# untitled.net
KiCad netlist of a schematic drawn in EAGLE
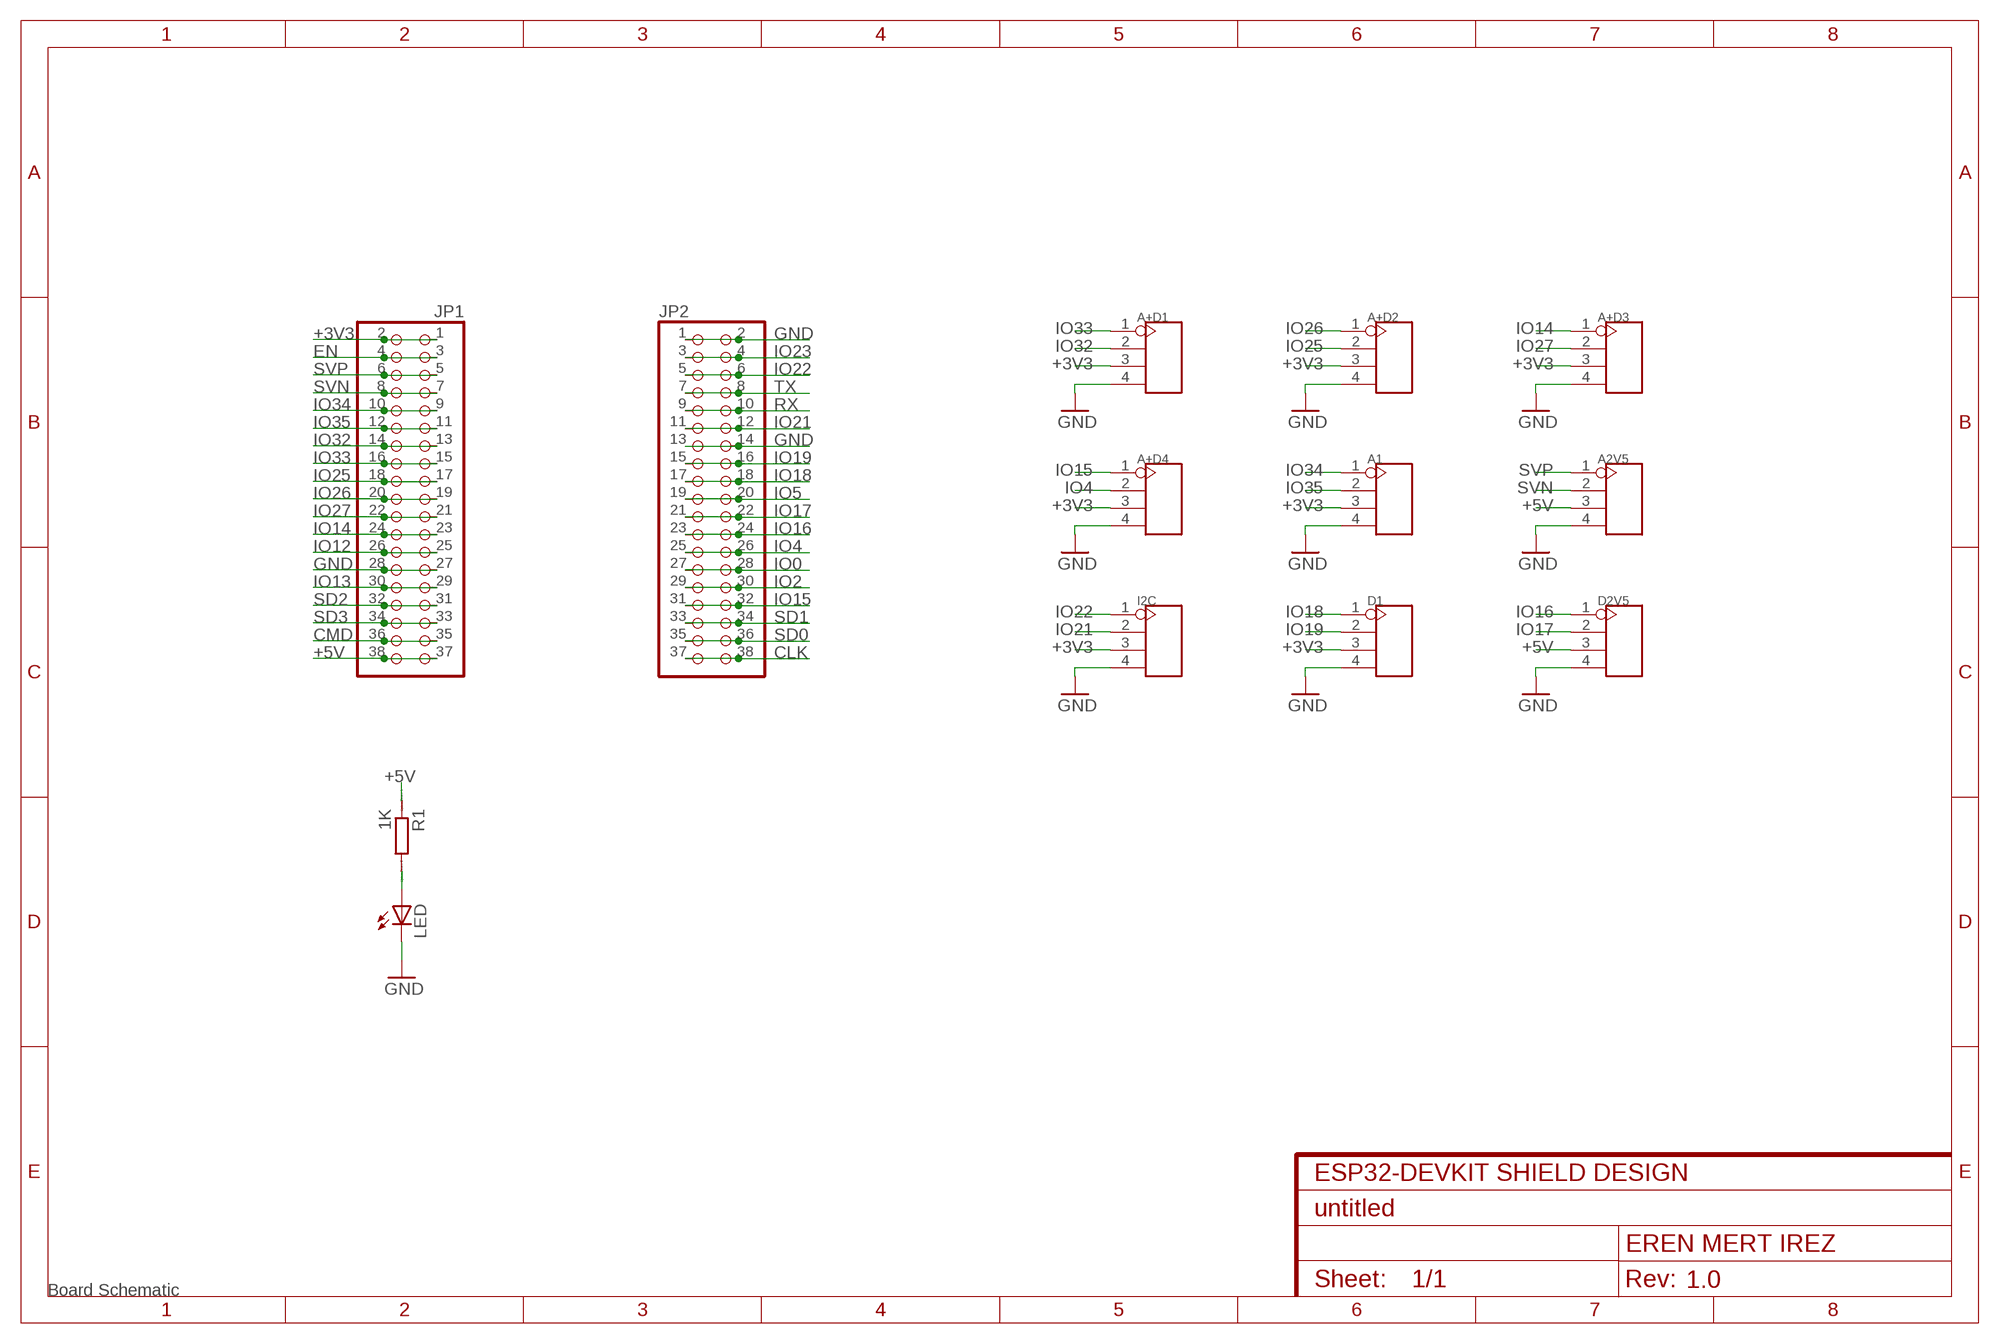
[diagram p0: schematic, sheet 1]

(export (version "E")
  (design (tool "Eeschema 10.0.6"))
  (components
    (comp (ref "A+D1")
      (value "HEADER-4P-80/40MIL")
      (footprint "eagle-import:4P-2.54-80_40MIL")
      (libsource (lib "eagle-import") (part "HEADER-4P-80/40MIL"))
    )
    (comp (ref "A+D2")
      (value "HEADER-4P-80/40MIL")
      (footprint "eagle-import:4P-2.54-80_40MIL")
      (libsource (lib "eagle-import") (part "HEADER-4P-80/40MIL"))
    )
    (comp (ref "A+D3")
      (value "HEADER-4P-80/40MIL")
      (footprint "eagle-import:4P-2.54-80_40MIL")
      (libsource (lib "eagle-import") (part "HEADER-4P-80/40MIL"))
    )
    (comp (ref "A+D4")
      (value "HEADER-4P-80/40MIL")
      (footprint "eagle-import:4P-2.54-80_40MIL")
      (libsource (lib "eagle-import") (part "HEADER-4P-80/40MIL"))
    )
    (comp (ref "A1")
      (value "HEADER-4P-80/40MIL")
      (footprint "eagle-import:4P-2.54-80_40MIL")
      (libsource (lib "eagle-import") (part "HEADER-4P-80/40MIL"))
    )
    (comp (ref "A2V5")
      (value "HEADER-4P-80/40MIL")
      (footprint "eagle-import:4P-2.54-80_40MIL")
      (libsource (lib "eagle-import") (part "HEADER-4P-80/40MIL"))
    )
    (comp (ref "D1")
      (value "HEADER-4P-80/40MIL")
      (footprint "eagle-import:4P-2.54-80_40MIL")
      (libsource (lib "eagle-import") (part "HEADER-4P-80/40MIL"))
    )
    (comp (ref "D2V5")
      (value "HEADER-4P-80/40MIL")
      (footprint "eagle-import:4P-2.54-80_40MIL")
      (libsource (lib "eagle-import") (part "HEADER-4P-80/40MIL"))
    )
    (comp (ref "I2C")
      (value "HEADER-4P-80/40MIL")
      (footprint "eagle-import:4P-2.54-80_40MIL")
      (libsource (lib "eagle-import") (part "HEADER-4P-80/40MIL"))
    )
    (comp (ref "JP1")
      (value "PINHD-2X19")
      (footprint "eagle-import:2X19")
      (libsource (lib "eagle-import") (part "PINHD-2X19"))
    )
    (comp (ref "JP2")
      (value "PINHD-2X19")
      (footprint "eagle-import:2X19")
      (libsource (lib "eagle-import") (part "PINHD-2X19"))
    )
    (comp (ref "LED")
      (value "LED3MM")
      (footprint "eagle-import:LED3MM")
      (libsource (lib "eagle-import") (part "LED3MM"))
    )
    (comp (ref "R1")
      (value "1K")
      (footprint "eagle-import:0207_10")
      (libsource (lib "eagle-import") (part "R0207/10"))
    )
  )
  (nets
    (net (code "1") (name "/+3V3") (class "Default")
      (node (ref "A+D1") (pin "3") (pinfunction "P$3_3") (pintype "bidirectional"))
      (node (ref "A+D2") (pin "3") (pinfunction "P$3_3") (pintype "bidirectional"))
      (node (ref "A+D3") (pin "3") (pinfunction "P$3_3") (pintype "bidirectional"))
      (node (ref "A+D4") (pin "3") (pinfunction "P$3_3") (pintype "bidirectional"))
      (node (ref "A1") (pin "3") (pinfunction "P$3_3") (pintype "bidirectional"))
      (node (ref "D1") (pin "3") (pinfunction "P$3_3") (pintype "bidirectional"))
      (node (ref "I2C") (pin "3") (pinfunction "P$3_3") (pintype "bidirectional"))
      (node (ref "JP1") (pin "1") (pinfunction "1_1") (pintype "passive"))
      (node (ref "JP1") (pin "2") (pinfunction "2_2") (pintype "passive"))
    )
    (net (code "2") (name "/+5V") (class "Default")
      (node (ref "A2V5") (pin "3") (pinfunction "P$3_3") (pintype "bidirectional"))
      (node (ref "D2V5") (pin "3") (pinfunction "P$3_3") (pintype "bidirectional"))
      (node (ref "JP1") (pin "37") (pinfunction "37_37") (pintype "passive"))
      (node (ref "JP1") (pin "38") (pinfunction "38_38") (pintype "passive"))
      (node (ref "R1") (pin "1") (pinfunction "1_1") (pintype "passive"))
    )
    (net (code "3") (name "/CLK") (class "Default")
      (node (ref "JP2") (pin "37") (pinfunction "37_37") (pintype "passive"))
      (node (ref "JP2") (pin "38") (pinfunction "38_38") (pintype "passive"))
    )
    (net (code "4") (name "/CMD") (class "Default")
      (node (ref "JP1") (pin "35") (pinfunction "35_35") (pintype "passive"))
      (node (ref "JP1") (pin "36") (pinfunction "36_36") (pintype "passive"))
    )
    (net (code "5") (name "/EN") (class "Default")
      (node (ref "JP1") (pin "3") (pinfunction "3_3") (pintype "passive"))
      (node (ref "JP1") (pin "4") (pinfunction "4_4") (pintype "passive"))
    )
    (net (code "6") (name "/IO0") (class "Default")
      (node (ref "JP2") (pin "27") (pinfunction "27_27") (pintype "passive"))
      (node (ref "JP2") (pin "28") (pinfunction "28_28") (pintype "passive"))
    )
    (net (code "7") (name "/IO2") (class "Default")
      (node (ref "JP2") (pin "29") (pinfunction "29_29") (pintype "passive"))
      (node (ref "JP2") (pin "30") (pinfunction "30_30") (pintype "passive"))
    )
    (net (code "8") (name "/IO4") (class "Default")
      (node (ref "A+D4") (pin "2") (pinfunction "P$2_2") (pintype "bidirectional"))
      (node (ref "JP2") (pin "25") (pinfunction "25_25") (pintype "passive"))
      (node (ref "JP2") (pin "26") (pinfunction "26_26") (pintype "passive"))
    )
    (net (code "9") (name "/IO5") (class "Default")
      (node (ref "JP2") (pin "19") (pinfunction "19_19") (pintype "passive"))
      (node (ref "JP2") (pin "20") (pinfunction "20_20") (pintype "passive"))
    )
    (net (code "10") (name "/IO12") (class "Default")
      (node (ref "JP1") (pin "25") (pinfunction "25_25") (pintype "passive"))
      (node (ref "JP1") (pin "26") (pinfunction "26_26") (pintype "passive"))
    )
    (net (code "11") (name "/IO13") (class "Default")
      (node (ref "JP1") (pin "29") (pinfunction "29_29") (pintype "passive"))
      (node (ref "JP1") (pin "30") (pinfunction "30_30") (pintype "passive"))
    )
    (net (code "12") (name "/IO14") (class "Default")
      (node (ref "A+D3") (pin "1") (pinfunction "P$1_1") (pintype "bidirectional"))
      (node (ref "JP1") (pin "23") (pinfunction "23_23") (pintype "passive"))
      (node (ref "JP1") (pin "24") (pinfunction "24_24") (pintype "passive"))
    )
    (net (code "13") (name "/IO15") (class "Default")
      (node (ref "A+D4") (pin "1") (pinfunction "P$1_1") (pintype "bidirectional"))
      (node (ref "JP2") (pin "31") (pinfunction "31_31") (pintype "passive"))
      (node (ref "JP2") (pin "32") (pinfunction "32_32") (pintype "passive"))
    )
    (net (code "14") (name "/IO16") (class "Default")
      (node (ref "D2V5") (pin "1") (pinfunction "P$1_1") (pintype "bidirectional"))
      (node (ref "JP2") (pin "23") (pinfunction "23_23") (pintype "passive"))
      (node (ref "JP2") (pin "24") (pinfunction "24_24") (pintype "passive"))
    )
    (net (code "15") (name "/IO17") (class "Default")
      (node (ref "D2V5") (pin "2") (pinfunction "P$2_2") (pintype "bidirectional"))
      (node (ref "JP2") (pin "21") (pinfunction "21_21") (pintype "passive"))
      (node (ref "JP2") (pin "22") (pinfunction "22_22") (pintype "passive"))
    )
    (net (code "16") (name "/IO18") (class "Default")
      (node (ref "D1") (pin "1") (pinfunction "P$1_1") (pintype "bidirectional"))
      (node (ref "JP2") (pin "17") (pinfunction "17_17") (pintype "passive"))
      (node (ref "JP2") (pin "18") (pinfunction "18_18") (pintype "passive"))
    )
    (net (code "17") (name "/IO19") (class "Default")
      (node (ref "D1") (pin "2") (pinfunction "P$2_2") (pintype "bidirectional"))
      (node (ref "JP2") (pin "15") (pinfunction "15_15") (pintype "passive"))
      (node (ref "JP2") (pin "16") (pinfunction "16_16") (pintype "passive"))
    )
    (net (code "18") (name "/IO21") (class "Default")
      (node (ref "I2C") (pin "2") (pinfunction "P$2_2") (pintype "bidirectional"))
      (node (ref "JP2") (pin "11") (pinfunction "11_11") (pintype "passive"))
      (node (ref "JP2") (pin "12") (pinfunction "12_12") (pintype "passive"))
    )
    (net (code "19") (name "/IO22") (class "Default")
      (node (ref "I2C") (pin "1") (pinfunction "P$1_1") (pintype "bidirectional"))
      (node (ref "JP2") (pin "5") (pinfunction "5_5") (pintype "passive"))
      (node (ref "JP2") (pin "6") (pinfunction "6_6") (pintype "passive"))
    )
    (net (code "20") (name "/IO23") (class "Default")
      (node (ref "JP2") (pin "3") (pinfunction "3_3") (pintype "passive"))
      (node (ref "JP2") (pin "4") (pinfunction "4_4") (pintype "passive"))
    )
    (net (code "21") (name "/IO25") (class "Default")
      (node (ref "A+D2") (pin "2") (pinfunction "P$2_2") (pintype "bidirectional"))
      (node (ref "JP1") (pin "17") (pinfunction "17_17") (pintype "passive"))
      (node (ref "JP1") (pin "18") (pinfunction "18_18") (pintype "passive"))
    )
    (net (code "22") (name "/IO26") (class "Default")
      (node (ref "A+D2") (pin "1") (pinfunction "P$1_1") (pintype "bidirectional"))
      (node (ref "JP1") (pin "19") (pinfunction "19_19") (pintype "passive"))
      (node (ref "JP1") (pin "20") (pinfunction "20_20") (pintype "passive"))
    )
    (net (code "23") (name "/IO27") (class "Default")
      (node (ref "A+D3") (pin "2") (pinfunction "P$2_2") (pintype "bidirectional"))
      (node (ref "JP1") (pin "21") (pinfunction "21_21") (pintype "passive"))
      (node (ref "JP1") (pin "22") (pinfunction "22_22") (pintype "passive"))
    )
    (net (code "24") (name "/IO32") (class "Default")
      (node (ref "A+D1") (pin "2") (pinfunction "P$2_2") (pintype "bidirectional"))
      (node (ref "JP1") (pin "13") (pinfunction "13_13") (pintype "passive"))
      (node (ref "JP1") (pin "14") (pinfunction "14_14") (pintype "passive"))
    )
    (net (code "25") (name "/IO33") (class "Default")
      (node (ref "A+D1") (pin "1") (pinfunction "P$1_1") (pintype "bidirectional"))
      (node (ref "JP1") (pin "15") (pinfunction "15_15") (pintype "passive"))
      (node (ref "JP1") (pin "16") (pinfunction "16_16") (pintype "passive"))
    )
    (net (code "26") (name "/IO34") (class "Default")
      (node (ref "A1") (pin "1") (pinfunction "P$1_1") (pintype "bidirectional"))
      (node (ref "JP1") (pin "10") (pinfunction "10_10") (pintype "passive"))
      (node (ref "JP1") (pin "9") (pinfunction "9_9") (pintype "passive"))
    )
    (net (code "27") (name "/IO35") (class "Default")
      (node (ref "A1") (pin "2") (pinfunction "P$2_2") (pintype "bidirectional"))
      (node (ref "JP1") (pin "11") (pinfunction "11_11") (pintype "passive"))
      (node (ref "JP1") (pin "12") (pinfunction "12_12") (pintype "passive"))
    )
    (net (code "28") (name "/RX") (class "Default")
      (node (ref "JP2") (pin "10") (pinfunction "10_10") (pintype "passive"))
      (node (ref "JP2") (pin "9") (pinfunction "9_9") (pintype "passive"))
    )
    (net (code "29") (name "/SD0") (class "Default")
      (node (ref "JP2") (pin "35") (pinfunction "35_35") (pintype "passive"))
      (node (ref "JP2") (pin "36") (pinfunction "36_36") (pintype "passive"))
    )
    (net (code "30") (name "/SD1") (class "Default")
      (node (ref "JP2") (pin "33") (pinfunction "33_33") (pintype "passive"))
      (node (ref "JP2") (pin "34") (pinfunction "34_34") (pintype "passive"))
    )
    (net (code "31") (name "/SD2") (class "Default")
      (node (ref "JP1") (pin "31") (pinfunction "31_31") (pintype "passive"))
      (node (ref "JP1") (pin "32") (pinfunction "32_32") (pintype "passive"))
    )
    (net (code "32") (name "/SD3") (class "Default")
      (node (ref "JP1") (pin "33") (pinfunction "33_33") (pintype "passive"))
      (node (ref "JP1") (pin "34") (pinfunction "34_34") (pintype "passive"))
    )
    (net (code "33") (name "/SVN") (class "Default")
      (node (ref "A2V5") (pin "2") (pinfunction "P$2_2") (pintype "bidirectional"))
      (node (ref "JP1") (pin "7") (pinfunction "7_7") (pintype "passive"))
      (node (ref "JP1") (pin "8") (pinfunction "8_8") (pintype "passive"))
    )
    (net (code "34") (name "/SVP") (class "Default")
      (node (ref "A2V5") (pin "1") (pinfunction "P$1_1") (pintype "bidirectional"))
      (node (ref "JP1") (pin "5") (pinfunction "5_5") (pintype "passive"))
      (node (ref "JP1") (pin "6") (pinfunction "6_6") (pintype "passive"))
    )
    (net (code "35") (name "/TX") (class "Default")
      (node (ref "JP2") (pin "7") (pinfunction "7_7") (pintype "passive"))
      (node (ref "JP2") (pin "8") (pinfunction "8_8") (pintype "passive"))
    )
    (net (code "36") (name "GND") (class "Default")
      (node (ref "A+D1") (pin "4") (pinfunction "P$4_4") (pintype "bidirectional"))
      (node (ref "A+D2") (pin "4") (pinfunction "P$4_4") (pintype "bidirectional"))
      (node (ref "A+D3") (pin "4") (pinfunction "P$4_4") (pintype "bidirectional"))
      (node (ref "A+D4") (pin "4") (pinfunction "P$4_4") (pintype "bidirectional"))
      (node (ref "A1") (pin "4") (pinfunction "P$4_4") (pintype "bidirectional"))
      (node (ref "A2V5") (pin "4") (pinfunction "P$4_4") (pintype "bidirectional"))
      (node (ref "D1") (pin "4") (pinfunction "P$4_4") (pintype "bidirectional"))
      (node (ref "D2V5") (pin "4") (pinfunction "P$4_4") (pintype "bidirectional"))
      (node (ref "I2C") (pin "4") (pinfunction "P$4_4") (pintype "bidirectional"))
      (node (ref "JP1") (pin "27") (pinfunction "27_27") (pintype "passive"))
      (node (ref "JP1") (pin "28") (pinfunction "28_28") (pintype "passive"))
      (node (ref "JP2") (pin "1") (pinfunction "1_1") (pintype "passive"))
      (node (ref "JP2") (pin "13") (pinfunction "13_13") (pintype "passive"))
      (node (ref "JP2") (pin "14") (pinfunction "14_14") (pintype "passive"))
      (node (ref "JP2") (pin "2") (pinfunction "2_2") (pintype "passive"))
      (node (ref "LED") (pin "K") (pinfunction "C_K") (pintype "passive"))
    )
    (net (code "37") (name "Net-(LED-PadA)") (class "Default")
      (node (ref "LED") (pin "A") (pinfunction "A_A") (pintype "passive"))
      (node (ref "R1") (pin "2") (pinfunction "2_2") (pintype "passive"))
    )
  )
)
